# cardV2.net
KiCad netlist of a schematic drawn in EAGLE
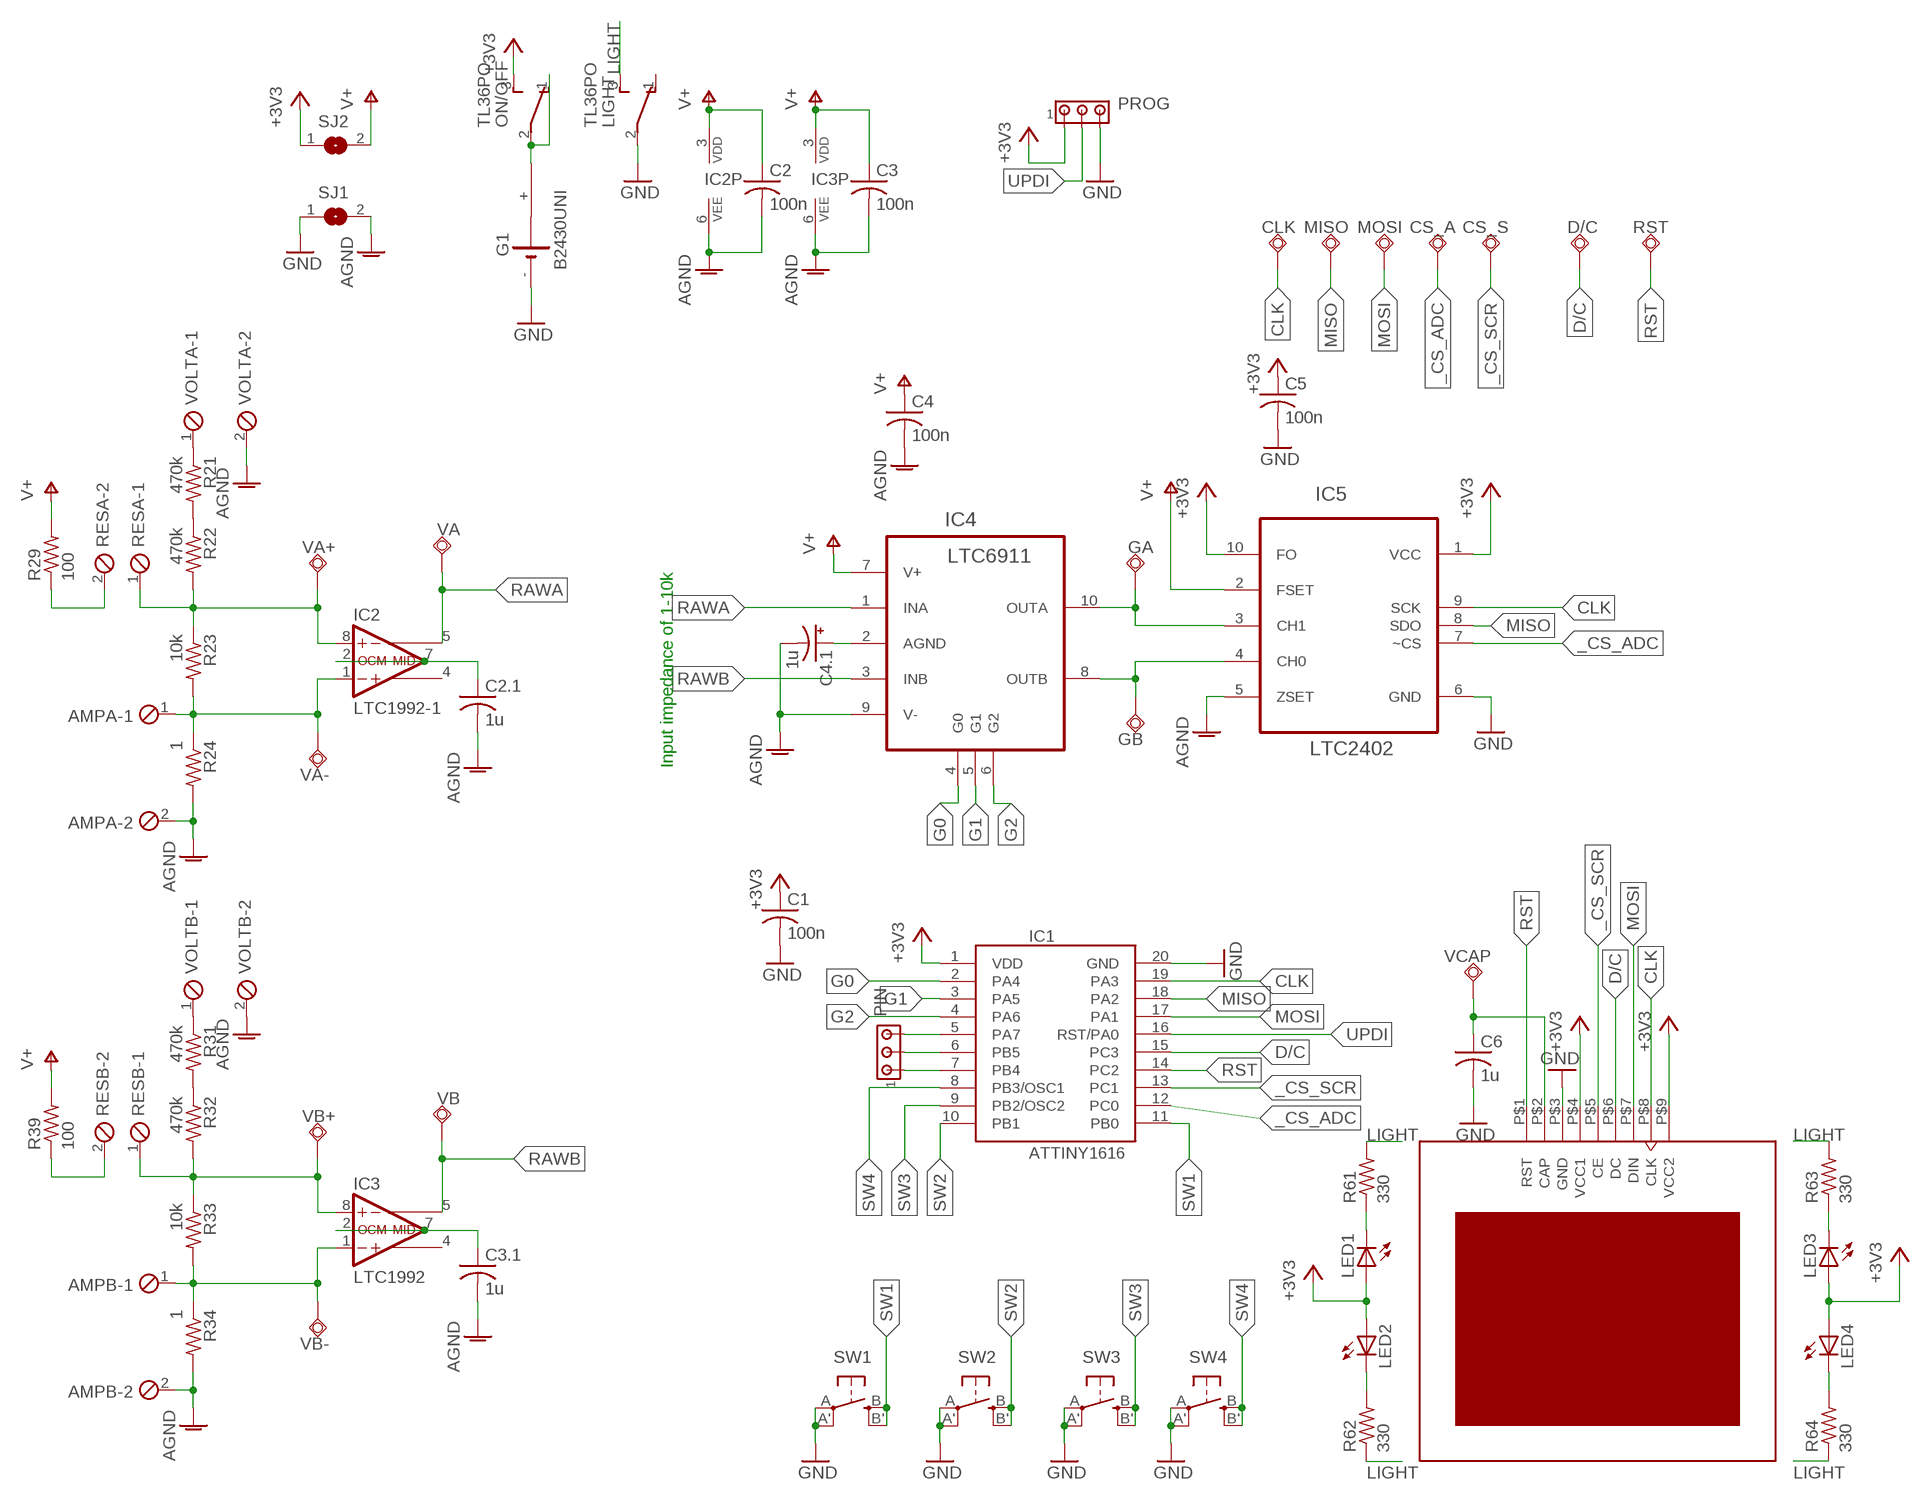
[diagram p0: schematic, sheet 1]

(export (version "E")
  (design (tool "Eeschema 10.0.6"))
  (components
    (comp (ref "AMPA")
      (value "MPT2")
      (footprint "eagle-import:2POL254")
      (libsource (lib "eagle-import") (part "MPT2"))
    )
    (comp (ref "AMPB")
      (value "MPT2")
      (footprint "eagle-import:2POL254")
      (libsource (lib "eagle-import") (part "MPT2"))
    )
    (comp (ref "C1")
      (value "100n")
      (footprint "eagle-import:C0805K")
      (libsource (lib "eagle-import") (part "C-USC0805K"))
    )
    (comp (ref "C2")
      (value "100n")
      (footprint "eagle-import:C0805K")
      (libsource (lib "eagle-import") (part "C-USC0805K"))
    )
    (comp (ref "C2.1")
      (value "1u")
      (footprint "eagle-import:C0805")
      (libsource (lib "eagle-import") (part "resistor_C-USC0805"))
    )
    (comp (ref "C3")
      (value "100n")
      (footprint "eagle-import:C0805K")
      (libsource (lib "eagle-import") (part "C-USC0805K"))
    )
    (comp (ref "C3.1")
      (value "1u")
      (footprint "eagle-import:C0805")
      (libsource (lib "eagle-import") (part "resistor_C-USC0805"))
    )
    (comp (ref "C4")
      (value "100n")
      (footprint "eagle-import:C0805K")
      (libsource (lib "eagle-import") (part "C-USC0805K"))
    )
    (comp (ref "C4.1")
      (value "1u")
      (footprint "eagle-import:A_3216-18R")
      (libsource (lib "eagle-import") (part "CPOL-USA/3216-18R"))
    )
    (comp (ref "C5")
      (value "100n")
      (footprint "eagle-import:C0805K")
      (libsource (lib "eagle-import") (part "C-USC0805K"))
    )
    (comp (ref "C6")
      (value "1u")
      (footprint "eagle-import:C0805")
      (libsource (lib "eagle-import") (part "resistor_C-USC0805"))
    )
    (comp (ref "CLK")
      (value "TPSQB1,27")
      (footprint "eagle-import:B1,27")
      (libsource (lib "eagle-import") (part "TPSQB1,27"))
    )
    (comp (ref "CS_A")
      (value "TPSQB1,27")
      (footprint "eagle-import:B1,27")
      (libsource (lib "eagle-import") (part "TPSQB1,27"))
    )
    (comp (ref "CS_S")
      (value "TPSQB1,27")
      (footprint "eagle-import:B1,27")
      (libsource (lib "eagle-import") (part "TPSQB1,27"))
    )
    (comp (ref "D/C")
      (value "TPSQB1,27")
      (footprint "eagle-import:B1,27")
      (libsource (lib "eagle-import") (part "TPSQB1,27"))
    )
    (comp (ref "G1")
      (value "B2430UNI")
      (footprint "eagle-import:B2430UNI")
      (libsource (lib "eagle-import") (part "B2430UNI"))
    )
    (comp (ref "GA")
      (value "TPSQB1,27")
      (footprint "eagle-import:B1,27")
      (libsource (lib "eagle-import") (part "TPSQB1,27"))
    )
    (comp (ref "GB")
      (value "TPSQB1,27")
      (footprint "eagle-import:B1,27")
      (libsource (lib "eagle-import") (part "TPSQB1,27"))
    )
    (comp (ref "IC1")
      (value "ATTINY1616")
      (footprint "eagle-import:SO20W")
      (libsource (lib "eagle-import") (part "ATTINY1616"))
    )
    (comp (ref "IC2")
      (value "LTC1992-1")
      (footprint "eagle-import:MSOP8")
      (libsource (lib "eagle-import") (part "LTC1992MS8C"))
    )
    (comp (ref "IC3")
      (value "LTC1992")
      (footprint "eagle-import:MSOP8")
      (libsource (lib "eagle-import") (part "LTC1992MS8C"))
    )
    (comp (ref "IC4")
      (value "LTC6911")
      (footprint "eagle-import:MSOP10")
      (libsource (lib "eagle-import") (part "LTC6911CMS-1"))
    )
    (comp (ref "IC5")
      (value "LTC2402")
      (footprint "eagle-import:MSOP10")
      (libsource (lib "eagle-import") (part "LTC2402CMS"))
    )
    (comp (ref "LED1")
      (value "LEDCHIP-LED0805")
      (footprint "eagle-import:CHIP-LED0805")
      (libsource (lib "eagle-import") (part "LEDCHIP-LED0805"))
    )
    (comp (ref "LED2")
      (value "LEDCHIP-LED0805")
      (footprint "eagle-import:CHIP-LED0805")
      (libsource (lib "eagle-import") (part "LEDCHIP-LED0805"))
    )
    (comp (ref "LED3")
      (value "LEDCHIP-LED0805")
      (footprint "eagle-import:CHIP-LED0805")
      (libsource (lib "eagle-import") (part "LEDCHIP-LED0805"))
    )
    (comp (ref "LED4")
      (value "LEDCHIP-LED0805")
      (footprint "eagle-import:CHIP-LED0805")
      (libsource (lib "eagle-import") (part "LEDCHIP-LED0805"))
    )
    (comp (ref "LIGHT")
      (value "TL36PO")
      (footprint "eagle-import:TL3XPO")
      (libsource (lib "eagle-import") (part "TL36PO"))
    )
    (comp (ref "MISO")
      (value "TPSQB1,27")
      (footprint "eagle-import:B1,27")
      (libsource (lib "eagle-import") (part "TPSQB1,27"))
    )
    (comp (ref "MOSI")
      (value "TPSQB1,27")
      (footprint "eagle-import:B1,27")
      (libsource (lib "eagle-import") (part "TPSQB1,27"))
    )
    (comp (ref "ON/OFF")
      (value "TL36PO")
      (footprint "eagle-import:TL3XPO")
      (libsource (lib "eagle-import") (part "TL36PO"))
    )
    (comp (ref "PIN")
      (value "MTA03-100")
      (footprint "eagle-import:10X03MTA")
      (libsource (lib "eagle-import") (part "MTA03-100"))
    )
    (comp (ref "PROG")
      (value "MTA03-100")
      (footprint "eagle-import:10X03MTA")
      (libsource (lib "eagle-import") (part "MTA03-100"))
    )
    (comp (ref "R21")
      (value "470k")
      (footprint "eagle-import:M0805")
      (libsource (lib "eagle-import") (part "R-US_M0805"))
    )
    (comp (ref "R22")
      (value "470k")
      (footprint "eagle-import:M0805")
      (libsource (lib "eagle-import") (part "R-US_M0805"))
    )
    (comp (ref "R23")
      (value "10k")
      (footprint "eagle-import:M0805")
      (libsource (lib "eagle-import") (part "R-US_M0805"))
    )
    (comp (ref "R24")
      (value "1")
      (footprint "eagle-import:M0805")
      (libsource (lib "eagle-import") (part "R-US_M0805"))
    )
    (comp (ref "R29")
      (value "100")
      (footprint "eagle-import:M0805")
      (libsource (lib "eagle-import") (part "R-US_M0805"))
    )
    (comp (ref "R31")
      (value "470k")
      (footprint "eagle-import:M0805")
      (libsource (lib "eagle-import") (part "R-US_M0805"))
    )
    (comp (ref "R32")
      (value "470k")
      (footprint "eagle-import:M0805")
      (libsource (lib "eagle-import") (part "R-US_M0805"))
    )
    (comp (ref "R33")
      (value "10k")
      (footprint "eagle-import:M0805")
      (libsource (lib "eagle-import") (part "R-US_M0805"))
    )
    (comp (ref "R34")
      (value "1")
      (footprint "eagle-import:M0805")
      (libsource (lib "eagle-import") (part "R-US_M0805"))
    )
    (comp (ref "R39")
      (value "100")
      (footprint "eagle-import:M0805")
      (libsource (lib "eagle-import") (part "R-US_M0805"))
    )
    (comp (ref "R61")
      (value "330")
      (footprint "eagle-import:M0805")
      (libsource (lib "eagle-import") (part "R-US_M0805"))
    )
    (comp (ref "R62")
      (value "330")
      (footprint "eagle-import:M0805")
      (libsource (lib "eagle-import") (part "R-US_M0805"))
    )
    (comp (ref "R63")
      (value "330")
      (footprint "eagle-import:M0805")
      (libsource (lib "eagle-import") (part "R-US_M0805"))
    )
    (comp (ref "R64")
      (value "330")
      (footprint "eagle-import:M0805")
      (libsource (lib "eagle-import") (part "R-US_M0805"))
    )
    (comp (ref "RESA")
      (value "MPT2")
      (footprint "eagle-import:2POL254")
      (libsource (lib "eagle-import") (part "MPT2"))
    )
    (comp (ref "RESB")
      (value "MPT2")
      (footprint "eagle-import:2POL254")
      (libsource (lib "eagle-import") (part "MPT2"))
    )
    (comp (ref "RST")
      (value "TPSQB1,27")
      (footprint "eagle-import:B1,27")
      (libsource (lib "eagle-import") (part "TPSQB1,27"))
    )
    (comp (ref "SJ1") (value "SJ") (footprint "eagle-import:SJ") (libsource (lib "eagle-import") (part "SJ")))
    (comp (ref "SJ2") (value "SJ") (footprint "eagle-import:SJ") (libsource (lib "eagle-import") (part "SJ")))
    (comp (ref "SW1")
      (value "SPST_TACT-EVQQ2")
      (footprint "eagle-import:EVQ-Q2")
      (libsource (lib "eagle-import") (part "SPST_TACT-EVQQ2"))
    )
    (comp (ref "SW2")
      (value "SPST_TACT-EVQQ2")
      (footprint "eagle-import:EVQ-Q2")
      (libsource (lib "eagle-import") (part "SPST_TACT-EVQQ2"))
    )
    (comp (ref "SW3")
      (value "SPST_TACT-EVQQ2")
      (footprint "eagle-import:EVQ-Q2")
      (libsource (lib "eagle-import") (part "SPST_TACT-EVQQ2"))
    )
    (comp (ref "SW4")
      (value "SPST_TACT-EVQQ2")
      (footprint "eagle-import:EVQ-Q2")
      (libsource (lib "eagle-import") (part "SPST_TACT-EVQQ2"))
    )
    (comp (ref "U$1")
      (value "NOKIA_SCREEN")
      (footprint "eagle-import:NOKIA_SCREEN")
      (libsource (lib "eagle-import") (part "NOKIA_SCREEN"))
    )
    (comp (ref "VA")
      (value "TPSQB1,27")
      (footprint "eagle-import:B1,27")
      (libsource (lib "eagle-import") (part "TPSQB1,27"))
    )
    (comp (ref "VA+")
      (value "TPSQB1,27")
      (footprint "eagle-import:B1,27")
      (libsource (lib "eagle-import") (part "TPSQB1,27"))
    )
    (comp (ref "VA-")
      (value "TPSQB1,27")
      (footprint "eagle-import:B1,27")
      (libsource (lib "eagle-import") (part "TPSQB1,27"))
    )
    (comp (ref "VB")
      (value "TPSQB1,27")
      (footprint "eagle-import:B1,27")
      (libsource (lib "eagle-import") (part "TPSQB1,27"))
    )
    (comp (ref "VB+")
      (value "TPSQB1,27")
      (footprint "eagle-import:B1,27")
      (libsource (lib "eagle-import") (part "TPSQB1,27"))
    )
    (comp (ref "VB-")
      (value "TPSQB1,27")
      (footprint "eagle-import:B1,27")
      (libsource (lib "eagle-import") (part "TPSQB1,27"))
    )
    (comp (ref "VCAP")
      (value "TPSQB1,27")
      (footprint "eagle-import:B1,27")
      (libsource (lib "eagle-import") (part "TPSQB1,27"))
    )
    (comp (ref "VOLTA")
      (value "MPT2")
      (footprint "eagle-import:2POL254")
      (libsource (lib "eagle-import") (part "MPT2"))
    )
    (comp (ref "VOLTB")
      (value "MPT2")
      (footprint "eagle-import:2POL254")
      (libsource (lib "eagle-import") (part "MPT2"))
    )
  )
  (nets
    (net (code "1") (name "+3V3") (class "Default")
      (node (ref "C1") (pin "1") (pinfunction "1_1") (pintype "passive"))
      (node (ref "C5") (pin "1") (pinfunction "1_1") (pintype "passive"))
      (node (ref "IC1") (pin "1") (pinfunction "VDD_1") (pintype "power_in"))
      (node (ref "IC5") (pin "1") (pinfunction "VCC_1") (pintype "power_in"))
      (node (ref "IC5") (pin "10") (pinfunction "FO_10") (pintype "input"))
      (node (ref "LED1") (pin "A") (pinfunction "A_A") (pintype "passive"))
      (node (ref "LED2") (pin "A") (pinfunction "A_A") (pintype "passive"))
      (node (ref "LED3") (pin "A") (pinfunction "A_A") (pintype "passive"))
      (node (ref "LED4") (pin "A") (pinfunction "A_A") (pintype "passive"))
      (node (ref "ON/OFF") (pin "3") (pinfunction "S_3") (pintype "passive"))
      (node (ref "PROG") (pin "1") (pinfunction "1_1") (pintype "passive"))
      (node (ref "SJ2") (pin "1") (pinfunction "1_1") (pintype "passive"))
      (node (ref "U$1") (pin "P$4") (pinfunction "VCC1_P$4") (pintype "power_in"))
      (node (ref "U$1") (pin "P$9") (pinfunction "VCC2_P$9") (pintype "power_in"))
    )
    (net (code "2") (name "/LIGHT") (class "Default")
      (node (ref "LIGHT") (pin "3") (pinfunction "S_3") (pintype "passive"))
      (node (ref "R61") (pin "2") (pinfunction "2_2") (pintype "passive"))
      (node (ref "R62") (pin "1") (pinfunction "1_1") (pintype "passive"))
      (node (ref "R63") (pin "2") (pinfunction "2_2") (pintype "passive"))
      (node (ref "R64") (pin "1") (pinfunction "1_1") (pintype "passive"))
    )
    (net (code "3") (name "AGND") (class "Default")
      (node (ref "AMPA") (pin "2") (pinfunction "1_2") (pintype "passive"))
      (node (ref "AMPB") (pin "2") (pinfunction "1_2") (pintype "passive"))
      (node (ref "C2") (pin "2") (pinfunction "2_2") (pintype "passive"))
      (node (ref "C2.1") (pin "2") (pinfunction "2_2") (pintype "passive"))
      (node (ref "C3") (pin "2") (pinfunction "2_2") (pintype "passive"))
      (node (ref "C3.1") (pin "2") (pinfunction "2_2") (pintype "passive"))
      (node (ref "C4") (pin "2") (pinfunction "2_2") (pintype "passive"))
      (node (ref "C4.1") (pin "-") (pinfunction "-_-") (pintype "passive"))
      (node (ref "IC2") (pin "6") (pinfunction "VEE_6") (pintype "power_in"))
      (node (ref "IC3") (pin "6") (pinfunction "VEE_6") (pintype "power_in"))
      (node (ref "IC4") (pin "9") (pinfunction "V-_9") (pintype "power_in"))
      (node (ref "IC5") (pin "5") (pinfunction "ZSET_5") (pintype "input"))
      (node (ref "R24") (pin "2") (pinfunction "2_2") (pintype "passive"))
      (node (ref "R34") (pin "2") (pinfunction "2_2") (pintype "passive"))
      (node (ref "SJ1") (pin "2") (pinfunction "2_2") (pintype "passive"))
      (node (ref "VOLTA") (pin "2") (pinfunction "1_2") (pintype "passive"))
      (node (ref "VOLTB") (pin "2") (pinfunction "1_2") (pintype "passive"))
    )
    (net (code "4") (name "CLK") (class "Default")
      (node (ref "CLK") (pin "TP") (pinfunction "TP_TP") (pintype "input"))
      (node (ref "IC1") (pin "19") (pinfunction "PA3_19") (pintype "bidirectional"))
      (node (ref "IC5") (pin "9") (pinfunction "SCK_9") (pintype "input"))
      (node (ref "U$1") (pin "P$8") (pinfunction "CLK_P$8") (pintype "input"))
    )
    (net (code "5") (name "D{slash}C") (class "Default")
      (node (ref "D/C") (pin "TP") (pinfunction "TP_TP") (pintype "input"))
      (node (ref "IC1") (pin "15") (pinfunction "PC3_15") (pintype "bidirectional"))
      (node (ref "U$1") (pin "P$6") (pinfunction "DC_P$6") (pintype "input"))
    )
    (net (code "6") (name "G0") (class "Default")
      (node (ref "IC1") (pin "2") (pinfunction "PA4_2") (pintype "bidirectional"))
      (node (ref "IC4") (pin "4") (pinfunction "G0_4") (pintype "input"))
    )
    (net (code "7") (name "G1") (class "Default")
      (node (ref "IC1") (pin "3") (pinfunction "PA5_3") (pintype "bidirectional"))
      (node (ref "IC4") (pin "5") (pinfunction "G1_5") (pintype "input"))
    )
    (net (code "8") (name "G2") (class "Default")
      (node (ref "IC1") (pin "4") (pinfunction "PA6_4") (pintype "bidirectional"))
      (node (ref "IC4") (pin "6") (pinfunction "G2_6") (pintype "input"))
    )
    (net (code "9") (name "GND") (class "Default")
      (node (ref "C1") (pin "2") (pinfunction "2_2") (pintype "passive"))
      (node (ref "C5") (pin "2") (pinfunction "2_2") (pintype "passive"))
      (node (ref "C6") (pin "2") (pinfunction "2_2") (pintype "passive"))
      (node (ref "G1") (pin "-") (pinfunction "-_-") (pintype "passive"))
      (node (ref "IC1") (pin "20") (pinfunction "GND_20") (pintype "power_in"))
      (node (ref "IC5") (pin "6") (pinfunction "GND_6") (pintype "passive"))
      (node (ref "LIGHT") (pin "2") (pinfunction "P_2") (pintype "passive"))
      (node (ref "PROG") (pin "3") (pinfunction "3_3") (pintype "passive"))
      (node (ref "SJ1") (pin "1") (pinfunction "1_1") (pintype "passive"))
      (node (ref "SW1") (pin "A") (pinfunction "P_A") (pintype "passive"))
      (node (ref "SW1") (pin "A'") (pinfunction "P1_A'") (pintype "passive"))
      (node (ref "SW2") (pin "A") (pinfunction "P_A") (pintype "passive"))
      (node (ref "SW2") (pin "A'") (pinfunction "P1_A'") (pintype "passive"))
      (node (ref "SW3") (pin "A") (pinfunction "P_A") (pintype "passive"))
      (node (ref "SW3") (pin "A'") (pinfunction "P1_A'") (pintype "passive"))
      (node (ref "SW4") (pin "A") (pinfunction "P_A") (pintype "passive"))
      (node (ref "SW4") (pin "A'") (pinfunction "P1_A'") (pintype "passive"))
      (node (ref "U$1") (pin "P$3") (pinfunction "GND_P$3") (pintype "power_in"))
    )
    (net (code "10") (name "MISO") (class "Default")
      (node (ref "IC1") (pin "18") (pinfunction "PA2_18") (pintype "bidirectional"))
      (node (ref "IC5") (pin "8") (pinfunction "SDO_8") (pintype "output"))
      (node (ref "MISO") (pin "TP") (pinfunction "TP_TP") (pintype "input"))
    )
    (net (code "11") (name "MOSI") (class "Default")
      (node (ref "IC1") (pin "17") (pinfunction "PA1_17") (pintype "bidirectional"))
      (node (ref "MOSI") (pin "TP") (pinfunction "TP_TP") (pintype "input"))
      (node (ref "U$1") (pin "P$7") (pinfunction "DIN_P$7") (pintype "input"))
    )
    (net (code "12") (name "Net-(IC1-PA7)") (class "Default")
      (node (ref "IC1") (pin "5") (pinfunction "PA7_5") (pintype "bidirectional"))
      (node (ref "PIN") (pin "3") (pinfunction "3_3") (pintype "passive"))
    )
    (net (code "13") (name "Net-(IC1-PB4)") (class "Default")
      (node (ref "IC1") (pin "7") (pinfunction "PB4_7") (pintype "bidirectional"))
      (node (ref "PIN") (pin "1") (pinfunction "1_1") (pintype "passive"))
    )
    (net (code "14") (name "Net-(IC1-PB5)") (class "Default")
      (node (ref "IC1") (pin "6") (pinfunction "PB5_6") (pintype "bidirectional"))
      (node (ref "PIN") (pin "2") (pinfunction "2_2") (pintype "passive"))
    )
    (net (code "15") (name "Net-(IC2A-+IN)") (class "Default")
      (node (ref "IC2") (pin "8") (pinfunction "+IN_8") (pintype "input"))
      (node (ref "R22") (pin "2") (pinfunction "2_2") (pintype "passive"))
      (node (ref "R23") (pin "1") (pinfunction "1_1") (pintype "passive"))
      (node (ref "RESA") (pin "1") (pinfunction "1_1") (pintype "passive"))
      (node (ref "VA+") (pin "TP") (pinfunction "TP_TP") (pintype "input"))
    )
    (net (code "16") (name "Net-(IC2A--IN)") (class "Default")
      (node (ref "AMPA") (pin "1") (pinfunction "1_1") (pintype "passive"))
      (node (ref "IC2") (pin "1") (pinfunction "-IN_1") (pintype "input"))
      (node (ref "R23") (pin "2") (pinfunction "2_2") (pintype "passive"))
      (node (ref "R24") (pin "1") (pinfunction "1_1") (pintype "passive"))
      (node (ref "VA-") (pin "TP") (pinfunction "TP_TP") (pintype "input"))
    )
    (net (code "17") (name "Net-(IC2A-MID)") (class "Default")
      (node (ref "C2.1") (pin "1") (pinfunction "1_1") (pintype "passive"))
      (node (ref "IC2") (pin "2") (pinfunction "OCM_2") (pintype "input"))
      (node (ref "IC2") (pin "7") (pinfunction "MID_7") (pintype "passive"))
    )
    (net (code "18") (name "Net-(IC3A-+IN)") (class "Default")
      (node (ref "IC3") (pin "8") (pinfunction "+IN_8") (pintype "input"))
      (node (ref "R32") (pin "2") (pinfunction "2_2") (pintype "passive"))
      (node (ref "R33") (pin "1") (pinfunction "1_1") (pintype "passive"))
      (node (ref "RESB") (pin "1") (pinfunction "1_1") (pintype "passive"))
      (node (ref "VB+") (pin "TP") (pinfunction "TP_TP") (pintype "input"))
    )
    (net (code "19") (name "Net-(IC3A--IN)") (class "Default")
      (node (ref "AMPB") (pin "1") (pinfunction "1_1") (pintype "passive"))
      (node (ref "IC3") (pin "1") (pinfunction "-IN_1") (pintype "input"))
      (node (ref "R33") (pin "2") (pinfunction "2_2") (pintype "passive"))
      (node (ref "R34") (pin "1") (pinfunction "1_1") (pintype "passive"))
      (node (ref "VB-") (pin "TP") (pinfunction "TP_TP") (pintype "input"))
    )
    (net (code "20") (name "Net-(IC3A-MID)") (class "Default")
      (node (ref "C3.1") (pin "1") (pinfunction "1_1") (pintype "passive"))
      (node (ref "IC3") (pin "2") (pinfunction "OCM_2") (pintype "input"))
      (node (ref "IC3") (pin "7") (pinfunction "MID_7") (pintype "passive"))
    )
    (net (code "21") (name "Net-(IC4-AGND)") (class "Default")
      (node (ref "C4.1") (pin "+") (pinfunction "+_+") (pintype "passive"))
      (node (ref "IC4") (pin "2") (pinfunction "AGND_2") (pintype "passive"))
    )
    (net (code "22") (name "Net-(IC4-OUTA)") (class "Default")
      (node (ref "GA") (pin "TP") (pinfunction "TP_TP") (pintype "input"))
      (node (ref "IC4") (pin "10") (pinfunction "OUTA_10") (pintype "output"))
      (node (ref "IC5") (pin "3") (pinfunction "CH1_3") (pintype "input"))
    )
    (net (code "23") (name "Net-(IC4-OUTB)") (class "Default")
      (node (ref "GB") (pin "TP") (pinfunction "TP_TP") (pintype "input"))
      (node (ref "IC4") (pin "8") (pinfunction "OUTB_8") (pintype "output"))
      (node (ref "IC5") (pin "4") (pinfunction "CH0_4") (pintype "input"))
    )
    (net (code "24") (name "Net-(LED1-PadC)") (class "Default")
      (node (ref "LED1") (pin "C") (pinfunction "C_C") (pintype "passive"))
      (node (ref "R61") (pin "1") (pinfunction "1_1") (pintype "passive"))
    )
    (net (code "25") (name "Net-(LED2-PadC)") (class "Default")
      (node (ref "LED2") (pin "C") (pinfunction "C_C") (pintype "passive"))
      (node (ref "R62") (pin "2") (pinfunction "2_2") (pintype "passive"))
    )
    (net (code "26") (name "Net-(LED3-PadC)") (class "Default")
      (node (ref "LED3") (pin "C") (pinfunction "C_C") (pintype "passive"))
      (node (ref "R63") (pin "1") (pinfunction "1_1") (pintype "passive"))
    )
    (net (code "27") (name "Net-(LED4-PadC)") (class "Default")
      (node (ref "LED4") (pin "C") (pinfunction "C_C") (pintype "passive"))
      (node (ref "R64") (pin "2") (pinfunction "2_2") (pintype "passive"))
    )
    (net (code "28") (name "Net-(ON/OFF-O)") (class "Default")
      (node (ref "G1") (pin "+") (pinfunction "+_+") (pintype "passive"))
      (node (ref "ON/OFF") (pin "1") (pinfunction "O_1") (pintype "passive"))
      (node (ref "ON/OFF") (pin "2") (pinfunction "P_2") (pintype "passive"))
    )
    (net (code "29") (name "Net-(R21-Pad1)") (class "Default")
      (node (ref "R21") (pin "1") (pinfunction "1_1") (pintype "passive"))
      (node (ref "VOLTA") (pin "1") (pinfunction "1_1") (pintype "passive"))
    )
    (net (code "30") (name "Net-(R21-Pad2)") (class "Default")
      (node (ref "R21") (pin "2") (pinfunction "2_2") (pintype "passive"))
      (node (ref "R22") (pin "1") (pinfunction "1_1") (pintype "passive"))
    )
    (net (code "31") (name "Net-(R31-Pad1)") (class "Default")
      (node (ref "R31") (pin "1") (pinfunction "1_1") (pintype "passive"))
      (node (ref "VOLTB") (pin "1") (pinfunction "1_1") (pintype "passive"))
    )
    (net (code "32") (name "Net-(R31-Pad2)") (class "Default")
      (node (ref "R31") (pin "2") (pinfunction "2_2") (pintype "passive"))
      (node (ref "R32") (pin "1") (pinfunction "1_1") (pintype "passive"))
    )
    (net (code "33") (name "Net-(RESAB-1)") (class "Default")
      (node (ref "R29") (pin "1") (pinfunction "1_1") (pintype "passive"))
      (node (ref "RESA") (pin "2") (pinfunction "1_2") (pintype "passive"))
    )
    (net (code "34") (name "Net-(RESBB-1)") (class "Default")
      (node (ref "R39") (pin "1") (pinfunction "1_1") (pintype "passive"))
      (node (ref "RESB") (pin "2") (pinfunction "1_2") (pintype "passive"))
    )
    (net (code "35") (name "Net-(U$1-CAP)") (class "Default")
      (node (ref "C6") (pin "1") (pinfunction "1_1") (pintype "passive"))
      (node (ref "U$1") (pin "P$2") (pinfunction "CAP_P$2") (pintype "passive"))
      (node (ref "VCAP") (pin "TP") (pinfunction "TP_TP") (pintype "input"))
    )
    (net (code "36") (name "RAWA") (class "Default")
      (node (ref "IC2") (pin "5") (pinfunction "-OUT_5") (pintype "output"))
      (node (ref "IC4") (pin "1") (pinfunction "INA_1") (pintype "input"))
      (node (ref "VA") (pin "TP") (pinfunction "TP_TP") (pintype "input"))
    )
    (net (code "37") (name "RAWB") (class "Default")
      (node (ref "IC3") (pin "5") (pinfunction "-OUT_5") (pintype "output"))
      (node (ref "IC4") (pin "3") (pinfunction "INB_3") (pintype "input"))
      (node (ref "VB") (pin "TP") (pinfunction "TP_TP") (pintype "input"))
    )
    (net (code "38") (name "RST") (class "Default")
      (node (ref "IC1") (pin "14") (pinfunction "PC2_14") (pintype "bidirectional"))
      (node (ref "RST") (pin "TP") (pinfunction "TP_TP") (pintype "input"))
      (node (ref "U$1") (pin "P$1") (pinfunction "RST_P$1") (pintype "input"))
    )
    (net (code "39") (name "SW1") (class "Default")
      (node (ref "IC1") (pin "11") (pinfunction "PB0_11") (pintype "bidirectional"))
      (node (ref "SW1") (pin "B") (pinfunction "S_B") (pintype "passive"))
      (node (ref "SW1") (pin "B'") (pinfunction "S1_B'") (pintype "passive"))
    )
    (net (code "40") (name "SW2") (class "Default")
      (node (ref "IC1") (pin "10") (pinfunction "PB1_10") (pintype "bidirectional"))
      (node (ref "SW2") (pin "B") (pinfunction "S_B") (pintype "passive"))
      (node (ref "SW2") (pin "B'") (pinfunction "S1_B'") (pintype "passive"))
    )
    (net (code "41") (name "SW3") (class "Default")
      (node (ref "IC1") (pin "9") (pinfunction "PB2/OSC2_9") (pintype "bidirectional"))
      (node (ref "SW3") (pin "B") (pinfunction "S_B") (pintype "passive"))
      (node (ref "SW3") (pin "B'") (pinfunction "S1_B'") (pintype "passive"))
    )
    (net (code "42") (name "SW4") (class "Default")
      (node (ref "IC1") (pin "8") (pinfunction "PB3/OSC1_8") (pintype "bidirectional"))
      (node (ref "SW4") (pin "B") (pinfunction "S_B") (pintype "passive"))
      (node (ref "SW4") (pin "B'") (pinfunction "S1_B'") (pintype "passive"))
    )
    (net (code "43") (name "UPDI") (class "Default")
      (node (ref "IC1") (pin "16") (pinfunction "RST/PA0_16") (pintype "bidirectional"))
      (node (ref "PROG") (pin "2") (pinfunction "2_2") (pintype "passive"))
    )
    (net (code "44") (name "V+") (class "Default")
      (node (ref "C2") (pin "1") (pinfunction "1_1") (pintype "passive"))
      (node (ref "C3") (pin "1") (pinfunction "1_1") (pintype "passive"))
      (node (ref "C4") (pin "1") (pinfunction "1_1") (pintype "passive"))
      (node (ref "IC2") (pin "3") (pinfunction "VDD_3") (pintype "power_in"))
      (node (ref "IC3") (pin "3") (pinfunction "VDD_3") (pintype "power_in"))
      (node (ref "IC4") (pin "7") (pinfunction "V+_7") (pintype "power_in"))
      (node (ref "IC5") (pin "2") (pinfunction "FSET_2") (pintype "input"))
      (node (ref "R29") (pin "2") (pinfunction "2_2") (pintype "passive"))
      (node (ref "R39") (pin "2") (pinfunction "2_2") (pintype "passive"))
      (node (ref "SJ2") (pin "2") (pinfunction "2_2") (pintype "passive"))
    )
    (net (code "45") (name "_CS_ADC") (class "Default")
      (node (ref "CS_A") (pin "TP") (pinfunction "TP_TP") (pintype "input"))
      (node (ref "IC1") (pin "12") (pinfunction "PC0_12") (pintype "bidirectional"))
      (node (ref "IC5") (pin "7") (pinfunction "~{CS}_7") (pintype "input"))
    )
    (net (code "46") (name "_CS_SCR") (class "Default")
      (node (ref "CS_S") (pin "TP") (pinfunction "TP_TP") (pintype "input"))
      (node (ref "IC1") (pin "13") (pinfunction "PC1_13") (pintype "bidirectional"))
      (node (ref "U$1") (pin "P$5") (pinfunction "CE_P$5") (pintype "input"))
    )
    (net (code "47") (name "unconnected-(G1-+-Pad+@1)") (class "Default")
      (node (ref "G1") (pin "+@1") (pinfunction "+_+@1") (pintype "passive"))
    )
    (net (code "48") (name "unconnected-(G1-+-Pad+@2)") (class "Default")
      (node (ref "G1") (pin "+@2") (pinfunction "+_+@2") (pintype "passive"))
    )
    (net (code "49") (name "unconnected-(G1-+-Pad+@3)") (class "Default")
      (node (ref "G1") (pin "+@3") (pinfunction "+_+@3") (pintype "passive"))
    )
    (net (code "50") (name "unconnected-(G1-+-Pad+@4)") (class "Default")
      (node (ref "G1") (pin "+@4") (pinfunction "+_+@4") (pintype "passive"))
    )
    (net (code "51") (name "unconnected-(G1---Pad-@1)") (class "Default")
      (node (ref "G1") (pin "-@1") (pinfunction "-_-@1") (pintype "passive"))
    )
    (net (code "52") (name "unconnected-(IC2A-+OUT-Pad4)") (class "Default")
      (node (ref "IC2") (pin "4") (pinfunction "+OUT_4") (pintype "output"))
    )
    (net (code "53") (name "unconnected-(IC3A-+OUT-Pad4)") (class "Default")
      (node (ref "IC3") (pin "4") (pinfunction "+OUT_4") (pintype "output"))
    )
    (net (code "54") (name "unconnected-(LIGHT-O-Pad1)") (class "Default")
      (node (ref "LIGHT") (pin "1") (pinfunction "O_1") (pintype "passive"))
    )
  )
)
